# MM8I_Mk2.net
KiCad netlist of a schematic drawn in EAGLE
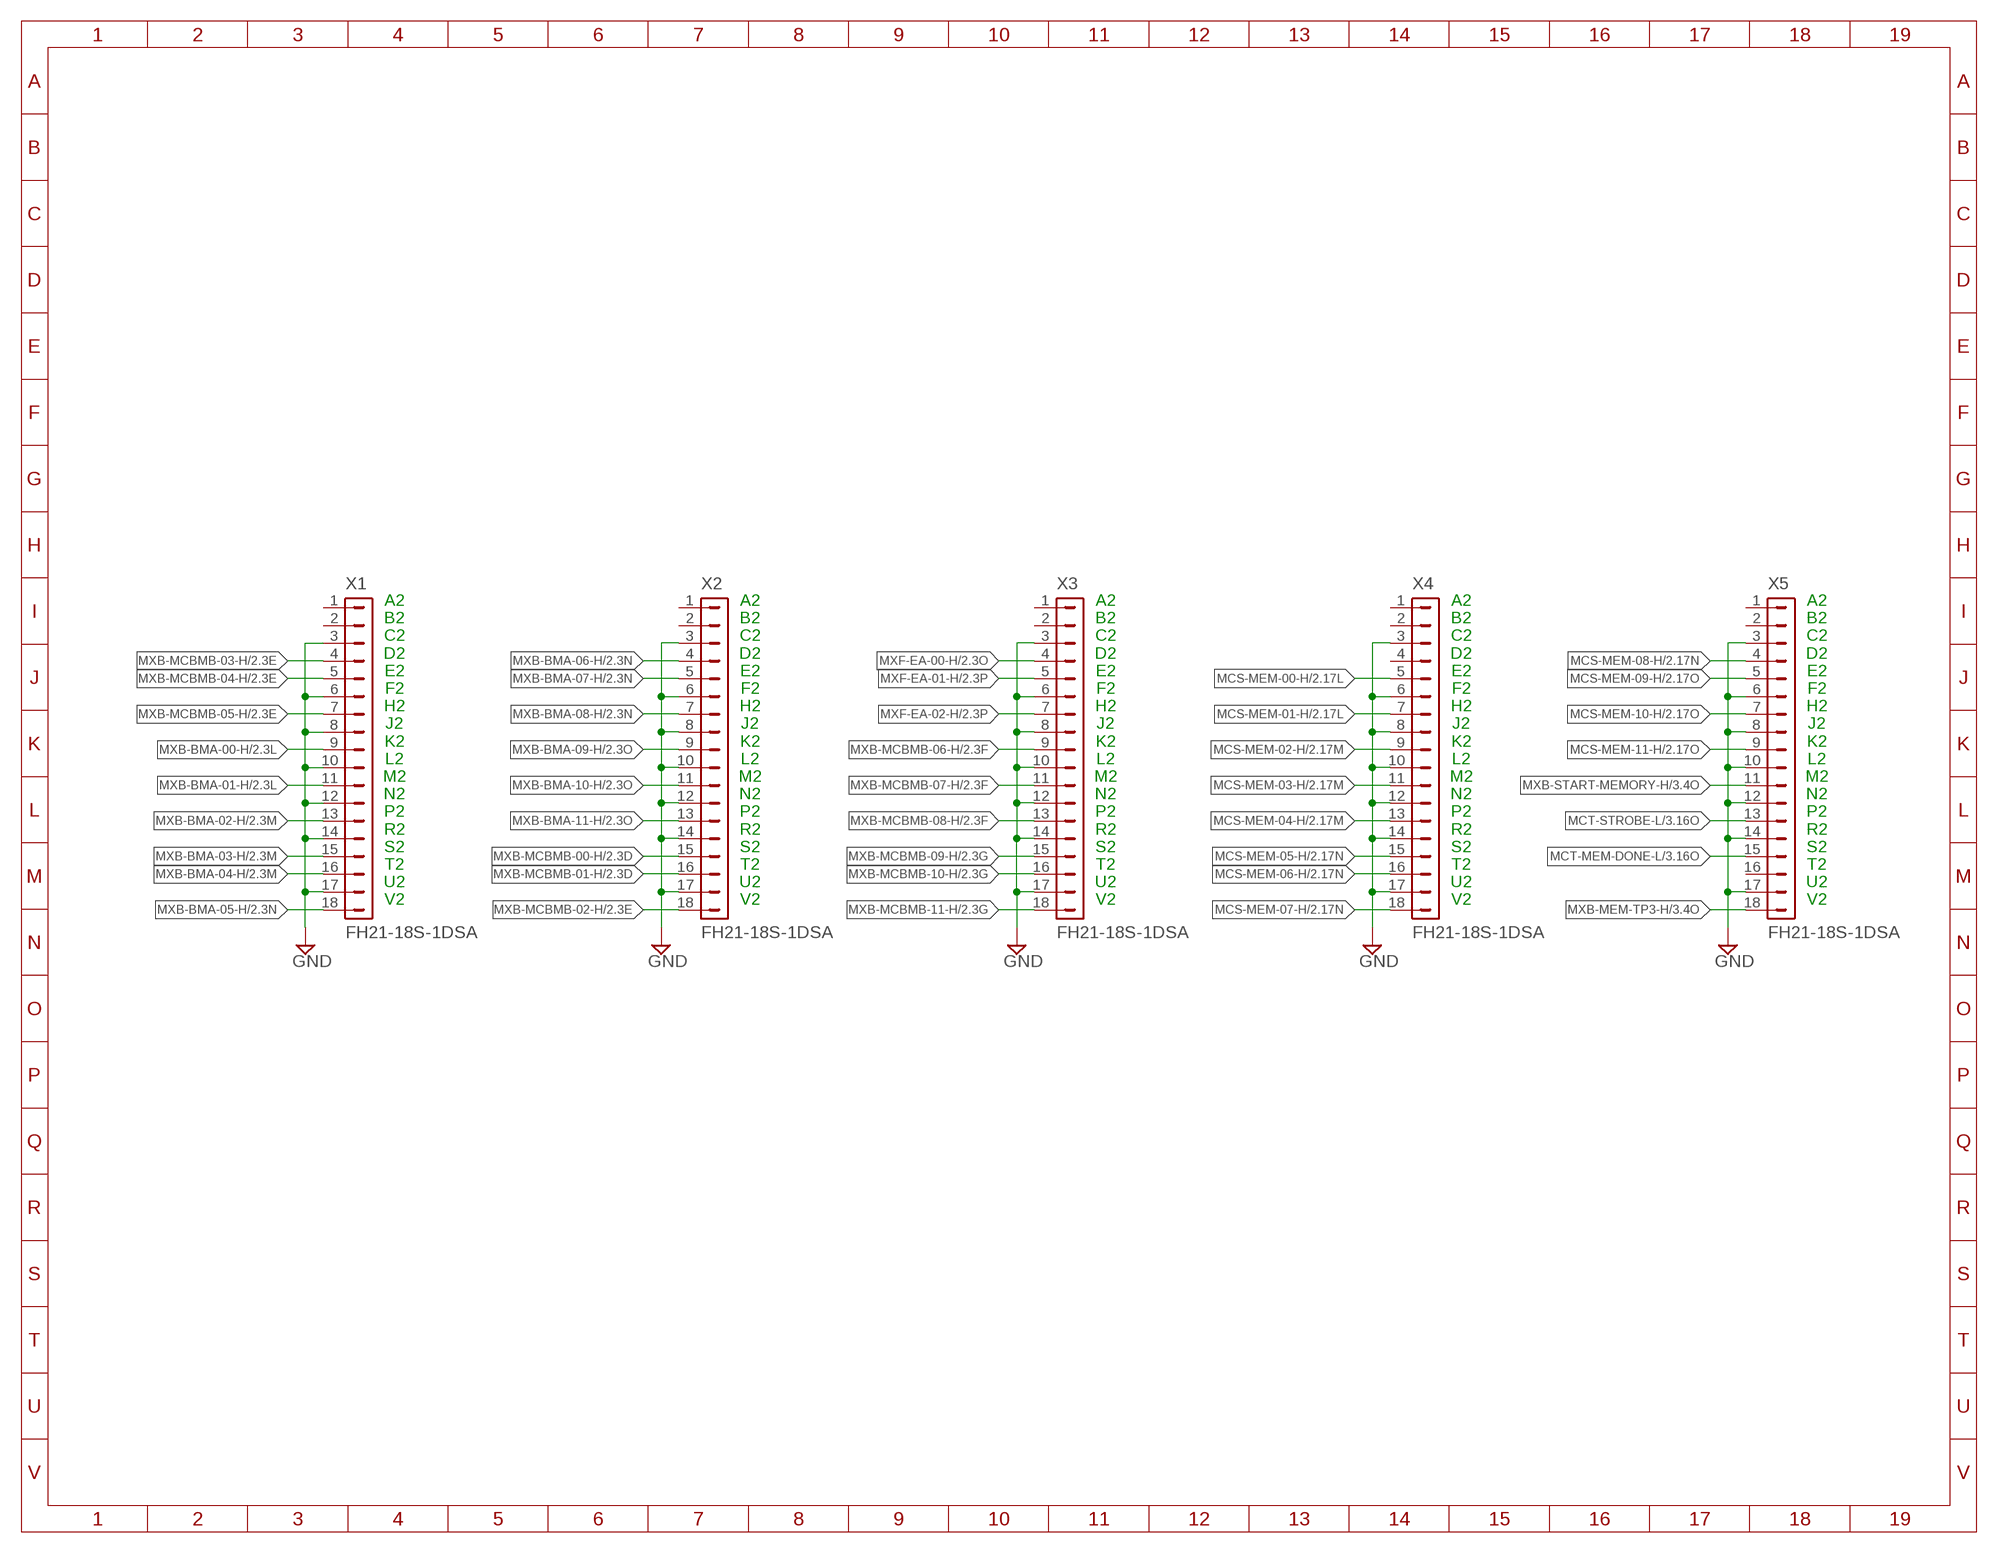
[diagram p0: schematic, sheet 1]
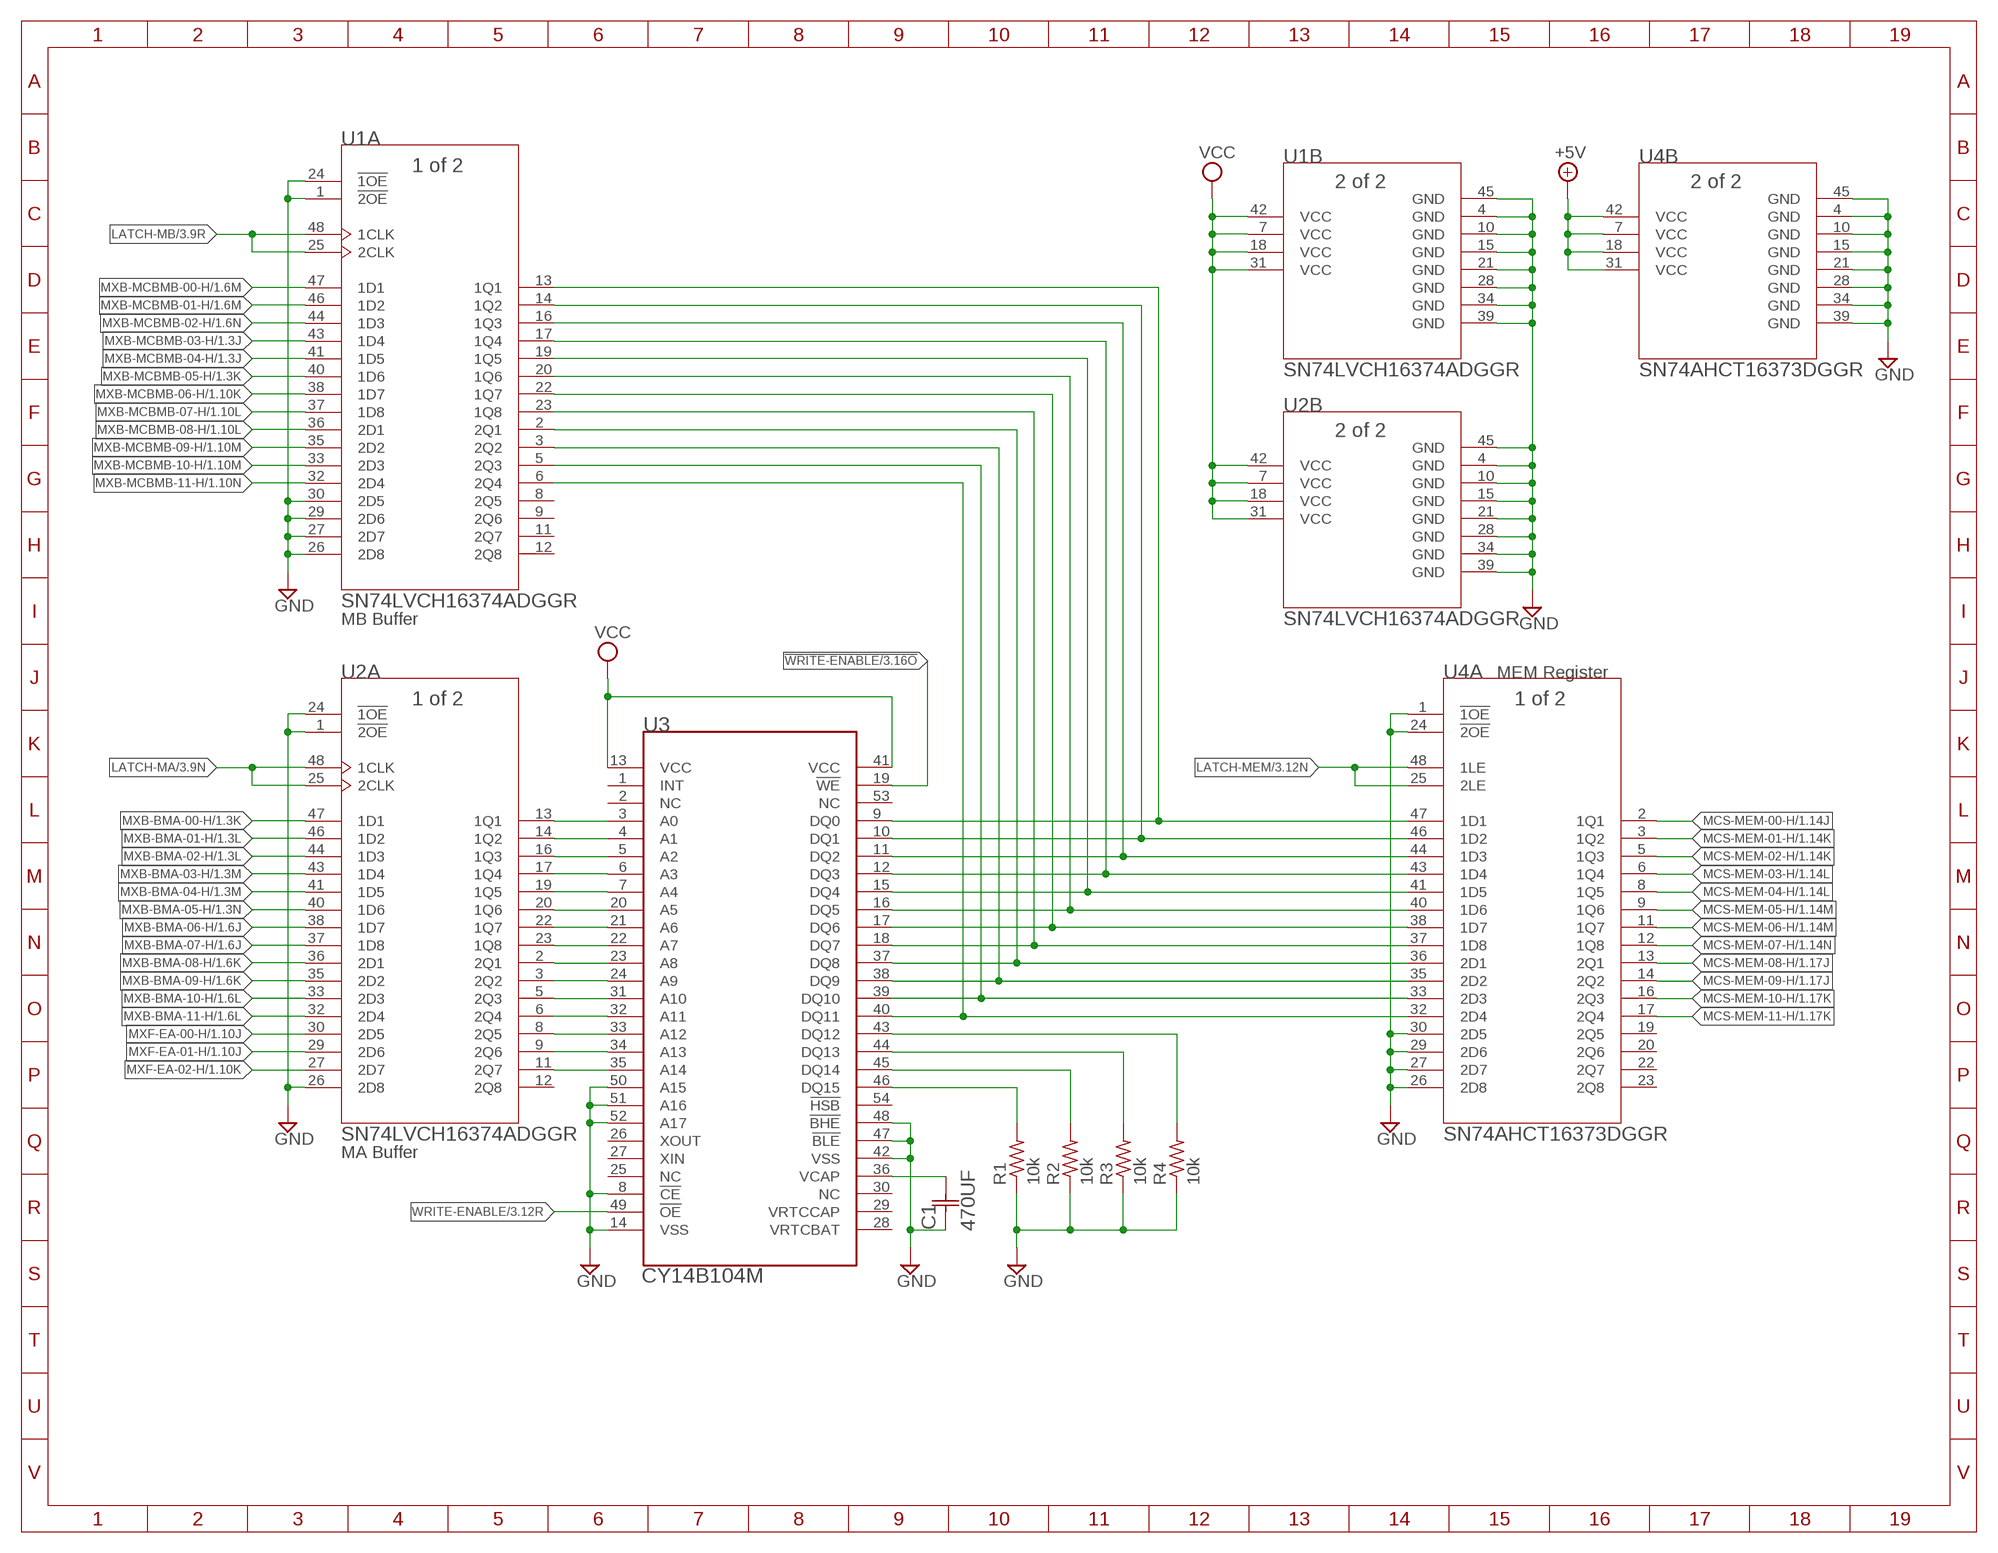
[diagram p1: schematic, sheet 2]
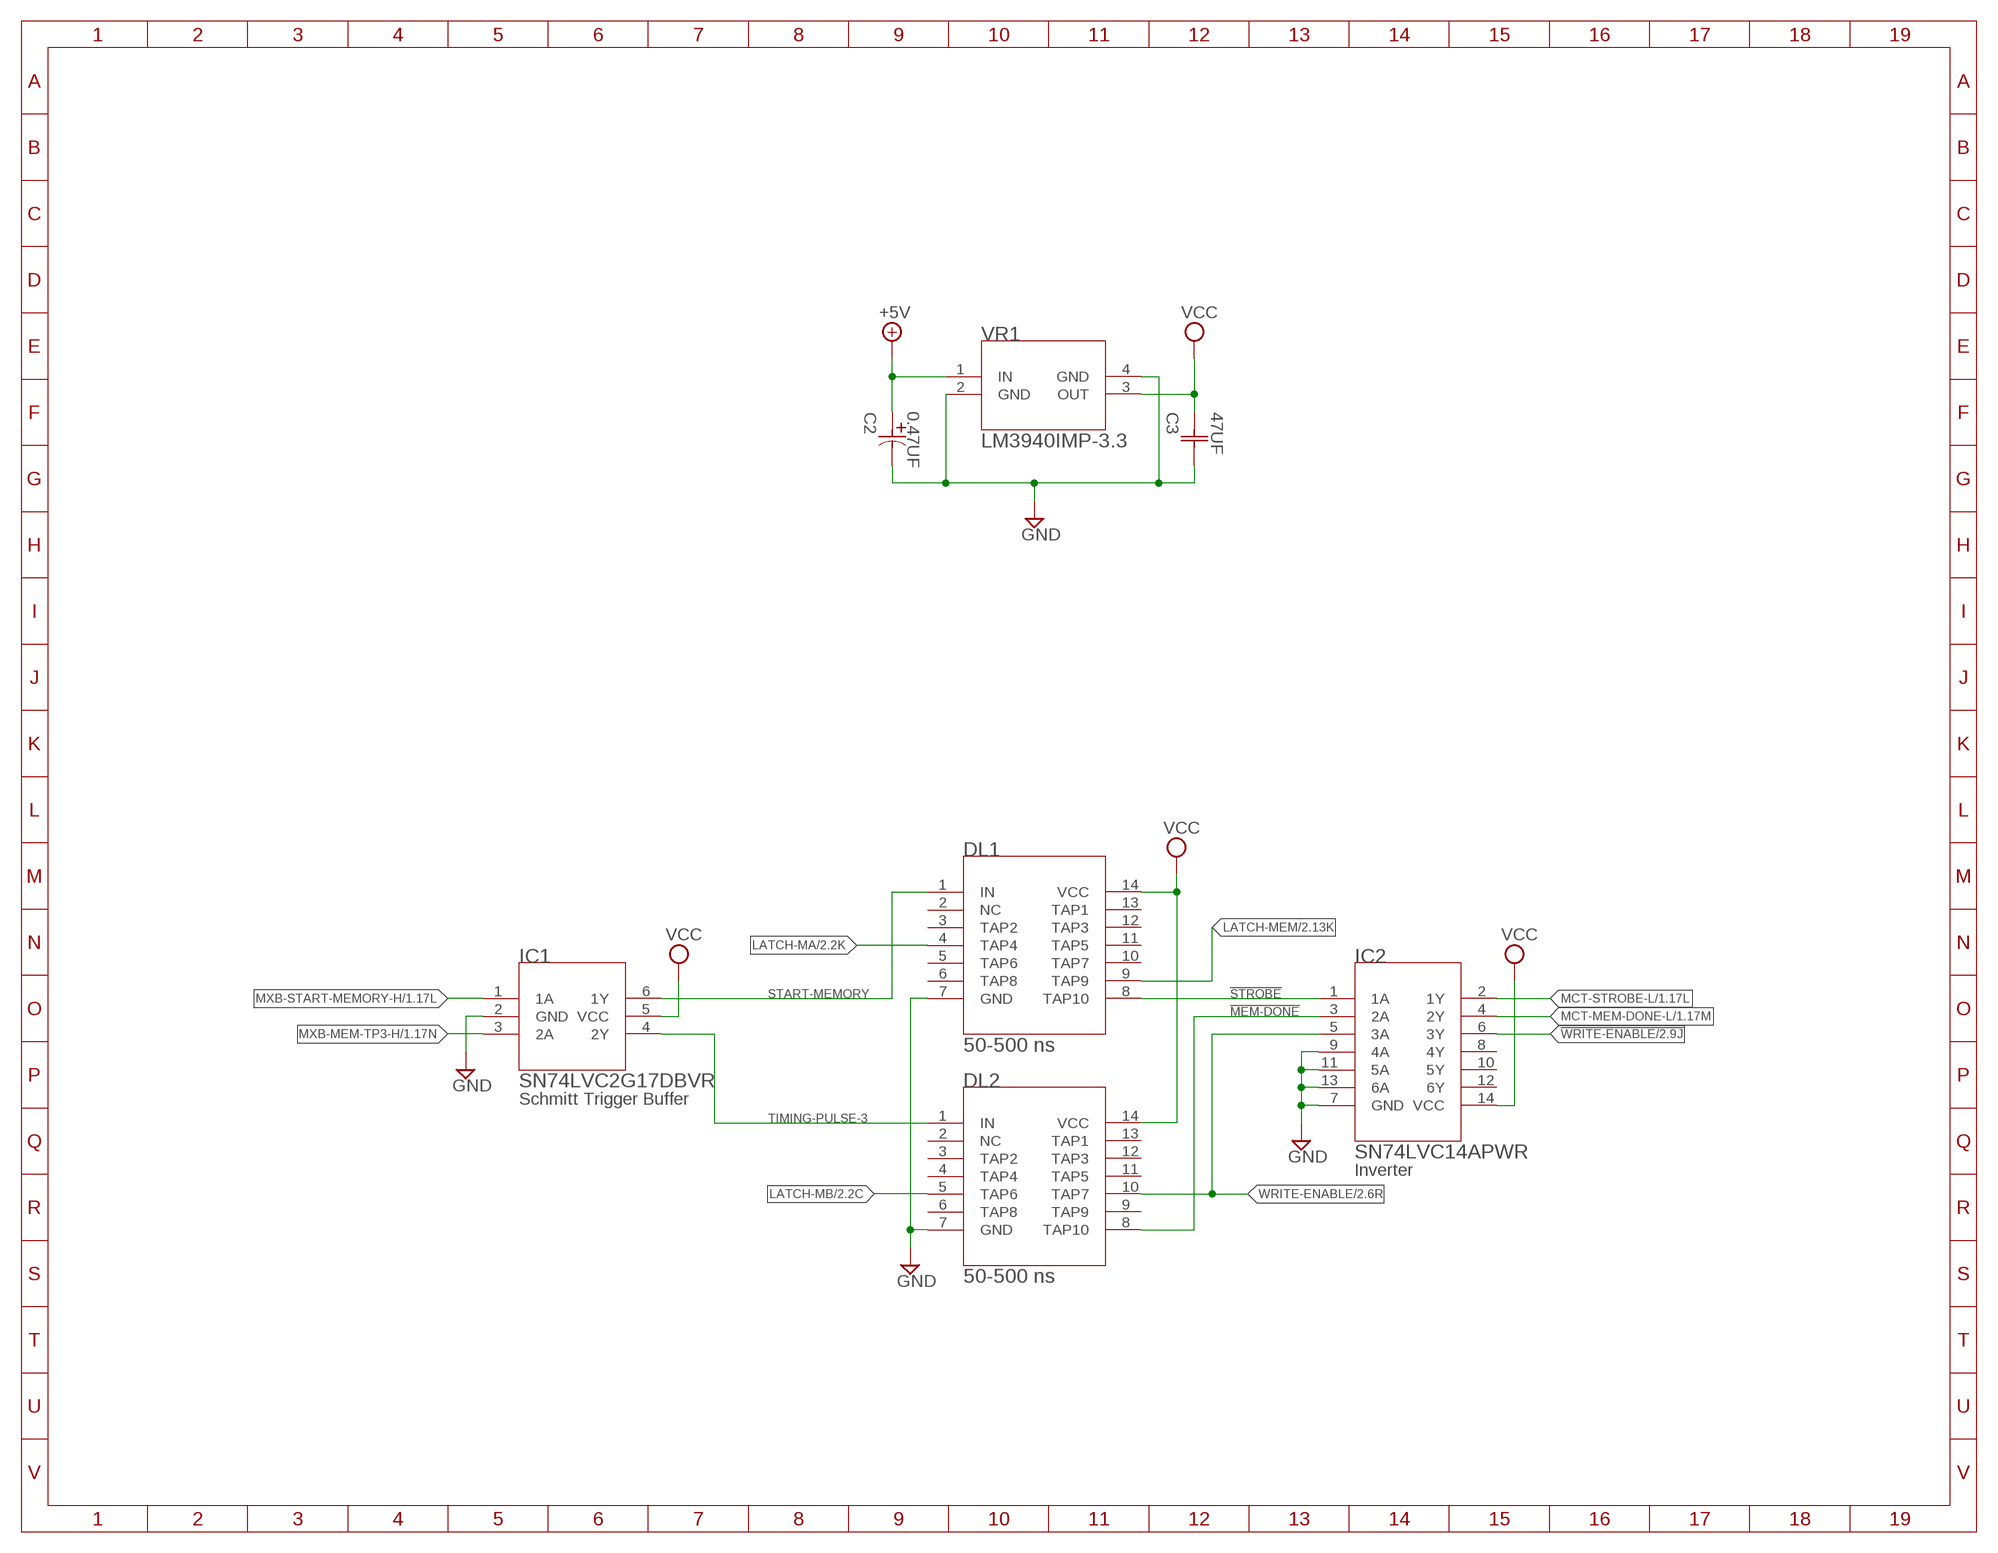
[diagram p2: schematic, sheet 3]

(export (version "E")
  (design (tool "Eeschema 10.0.6"))
  (components
    (comp (ref "X1")
      (value "FH21-18S-1DSA")
      (footprint "eagle-import:FH21-18S-1DSA")
      (libsource (lib "eagle-import") (part "FH21-18S-1DSA"))
    )
    (comp (ref "X2")
      (value "FH21-18S-1DSA")
      (footprint "eagle-import:FH21-18S-1DSA")
      (libsource (lib "eagle-import") (part "FH21-18S-1DSA"))
    )
    (comp (ref "X3")
      (value "FH21-18S-1DSA")
      (footprint "eagle-import:FH21-18S-1DSA")
      (libsource (lib "eagle-import") (part "FH21-18S-1DSA"))
    )
    (comp (ref "X4")
      (value "FH21-18S-1DSA")
      (footprint "eagle-import:FH21-18S-1DSA")
      (libsource (lib "eagle-import") (part "FH21-18S-1DSA"))
    )
    (comp (ref "X5")
      (value "FH21-18S-1DSA")
      (footprint "eagle-import:FH21-18S-1DSA")
      (libsource (lib "eagle-import") (part "FH21-18S-1DSA"))
    )
    (comp (ref "C1")
      (value "470UF")
      (footprint "eagle-import:CAPCP7343X430N")
      (fields (field (name "MPN") "NOSE477M004R0100"))
      (libsource (lib "eagle-import") (part "NOSE477M004R0100"))
    )
    (comp (ref "R1")
      (value "10k")
      (footprint "eagle-import:R1206")
      (libsource (lib "eagle-import") (part "R-US_R1206"))
    )
    (comp (ref "R2")
      (value "10k")
      (footprint "eagle-import:R1206")
      (libsource (lib "eagle-import") (part "R-US_R1206"))
    )
    (comp (ref "R3")
      (value "10k")
      (footprint "eagle-import:R1206")
      (libsource (lib "eagle-import") (part "R-US_R1206"))
    )
    (comp (ref "R4")
      (value "10k")
      (footprint "eagle-import:R1206")
      (libsource (lib "eagle-import") (part "R-US_R1206"))
    )
    (comp (ref "U1")
      (value "SN74LVCH16374ADGGR")
      (footprint "eagle-import:DGG48")
      (libsource (lib "eagle-import") (part "SN74LVCH16374ADGGR"))
    )
    (comp (ref "U2")
      (value "SN74LVCH16374ADGGR")
      (footprint "eagle-import:DGG48")
      (libsource (lib "eagle-import") (part "SN74LVCH16374ADGGR"))
    )
    (comp (ref "U3")
      (value "CY14B104M")
      (footprint "eagle-import:TSOPII-54")
      (libsource (lib "eagle-import") (part "CY14B104M"))
    )
    (comp (ref "U4")
      (value "SN74AHCT16373DGGR")
      (footprint "eagle-import:DGG48")
      (fields (field (name "MANUFACTURER") "Texas Instruments"))
      (libsource (lib "eagle-import") (part "SN74AHCT16373DGGR"))
    )
    (comp (ref "C2")
      (value "0.47UF")
      (footprint "eagle-import:CC0603N")
      (fields (field (name "MANUFACTURER_PART_NUMBER") "C0603C474K8PACTU"))
      (libsource (lib "eagle-import") (part "C0603C474K8PACTU"))
    )
    (comp (ref "C3")
      (value "47UF")
      (footprint "eagle-import:NOJC")
      (fields (field (name "MANUFACTURER_PART_NUMBER") "NOJC476M010RWJ"))
      (libsource (lib "eagle-import") (part "NOJC476M010RWJ"))
    )
    (comp (ref "DL1")
      (value "50-500 ns")
      (footprint "eagle-import:21-0066J_14")
      (fields (field (name "MANUFACTURER_PART_NUMBER") "DS1110LE-100+"))
      (libsource (lib "eagle-import") (part "DS1110LE-500+"))
    )
    (comp (ref "DL2")
      (value "50-500 ns")
      (footprint "eagle-import:21-0066J_14")
      (fields (field (name "MANUFACTURER_PART_NUMBER") "DS1110LE-100+"))
      (libsource (lib "eagle-import") (part "DS1110LE-500+"))
    )
    (comp (ref "IC1")
      (value "SN74LVC2G17DBVR")
      (footprint "eagle-import:DBV6")
      (fields (field (name "MANUFACTURER") "Texas Instruments"))
      (libsource (lib "eagle-import") (part "SN74LVC2G17DBVR"))
    )
    (comp (ref "IC2")
      (value "SN74LVC14APWR")
      (footprint "eagle-import:PW14")
      (fields (field (name "MANUFACTURER") "Texas Instruments"))
      (libsource (lib "eagle-import") (part "SN74LVC14APWR"))
    )
    (comp (ref "VR1")
      (value "LM3940IMP-3.3")
      (footprint "eagle-import:MP04A")
      (fields (field (name "MANUFACTURER_PART_NUMBER") "LM3940IMP-3.3/NOPB"))
      (libsource (lib "eagle-import") (part "LM3940IMP-3.3"))
    )
  )
  (nets
    (net (code "1") (name "+5V") (class "Default")
      (node (ref "C2") (pin "1") (pinfunction "1_1") (pintype "passive"))
      (node (ref "U4") (pin "18") (pinfunction "VCC_18") (pintype "power_in"))
      (node (ref "U4") (pin "31") (pinfunction "VCC_31") (pintype "power_in"))
      (node (ref "U4") (pin "42") (pinfunction "VCC_42") (pintype "power_in"))
      (node (ref "U4") (pin "7") (pinfunction "VCC_7") (pintype "power_in"))
      (node (ref "VR1") (pin "1") (pinfunction "IN_1") (pintype "input"))
    )
    (net (code "2") (name "GND") (class "Default")
      (node (ref "C1") (pin "2") (pinfunction "C2_2") (pintype "passive"))
      (node (ref "C2") (pin "2") (pinfunction "2_2") (pintype "passive"))
      (node (ref "C3") (pin "2") (pinfunction "C2_2") (pintype "passive"))
      (node (ref "DL1") (pin "7") (pinfunction "GND_7") (pintype "power_in"))
      (node (ref "DL2") (pin "7") (pinfunction "GND_7") (pintype "power_in"))
      (node (ref "IC1") (pin "2") (pinfunction "GND_2") (pintype "power_in"))
      (node (ref "IC2") (pin "11") (pinfunction "5A_11") (pintype "input"))
      (node (ref "IC2") (pin "13") (pinfunction "6A_13") (pintype "input"))
      (node (ref "IC2") (pin "7") (pinfunction "GND_7") (pintype "power_in"))
      (node (ref "IC2") (pin "9") (pinfunction "4A_9") (pintype "input"))
      (node (ref "R1") (pin "1") (pinfunction "1_1") (pintype "passive"))
      (node (ref "R2") (pin "1") (pinfunction "1_1") (pintype "passive"))
      (node (ref "R3") (pin "1") (pinfunction "1_1") (pintype "passive"))
      (node (ref "R4") (pin "1") (pinfunction "1_1") (pintype "passive"))
      (node (ref "U1") (pin "1") (pinfunction "~{2OE}_1") (pintype "input"))
      (node (ref "U1") (pin "10") (pinfunction "GND_10") (pintype "power_in"))
      (node (ref "U1") (pin "15") (pinfunction "GND_15") (pintype "power_in"))
      (node (ref "U1") (pin "21") (pinfunction "GND_21") (pintype "power_in"))
      (node (ref "U1") (pin "24") (pinfunction "~{1OE}_24") (pintype "input"))
      (node (ref "U1") (pin "26") (pinfunction "2D8_26") (pintype "input"))
      (node (ref "U1") (pin "27") (pinfunction "2D7_27") (pintype "input"))
      (node (ref "U1") (pin "28") (pinfunction "GND_28") (pintype "power_in"))
      (node (ref "U1") (pin "29") (pinfunction "2D6_29") (pintype "input"))
      (node (ref "U1") (pin "30") (pinfunction "2D5_30") (pintype "input"))
      (node (ref "U1") (pin "34") (pinfunction "GND_34") (pintype "power_in"))
      (node (ref "U1") (pin "39") (pinfunction "GND_39") (pintype "power_in"))
      (node (ref "U1") (pin "4") (pinfunction "GND_4") (pintype "power_in"))
      (node (ref "U1") (pin "45") (pinfunction "GND_45") (pintype "power_in"))
      (node (ref "U2") (pin "1") (pinfunction "~{2OE}_1") (pintype "input"))
      (node (ref "U2") (pin "10") (pinfunction "GND_10") (pintype "power_in"))
      (node (ref "U2") (pin "15") (pinfunction "GND_15") (pintype "power_in"))
      (node (ref "U2") (pin "21") (pinfunction "GND_21") (pintype "power_in"))
      (node (ref "U2") (pin "24") (pinfunction "~{1OE}_24") (pintype "input"))
      (node (ref "U2") (pin "26") (pinfunction "2D8_26") (pintype "input"))
      (node (ref "U2") (pin "28") (pinfunction "GND_28") (pintype "power_in"))
      (node (ref "U2") (pin "34") (pinfunction "GND_34") (pintype "power_in"))
      (node (ref "U2") (pin "39") (pinfunction "GND_39") (pintype "power_in"))
      (node (ref "U2") (pin "4") (pinfunction "GND_4") (pintype "power_in"))
      (node (ref "U2") (pin "45") (pinfunction "GND_45") (pintype "power_in"))
      (node (ref "U3") (pin "14") (pinfunction "VSS_14") (pintype "power_in"))
      (node (ref "U3") (pin "42") (pinfunction "VSS_42") (pintype "power_in"))
      (node (ref "U3") (pin "47") (pinfunction "~{BLE}_47") (pintype "input"))
      (node (ref "U3") (pin "48") (pinfunction "~{BHE}_48") (pintype "input"))
      (node (ref "U3") (pin "50") (pinfunction "A15_50") (pintype "input"))
      (node (ref "U3") (pin "51") (pinfunction "A16_51") (pintype "input"))
      (node (ref "U3") (pin "52") (pinfunction "A17_52") (pintype "input"))
      (node (ref "U3") (pin "8") (pinfunction "~{CE}_8") (pintype "bidirectional"))
      (node (ref "U4") (pin "1") (pinfunction "~{1OE}_1") (pintype "input"))
      (node (ref "U4") (pin "10") (pinfunction "GND_10") (pintype "power_in"))
      (node (ref "U4") (pin "15") (pinfunction "GND_15") (pintype "power_in"))
      (node (ref "U4") (pin "21") (pinfunction "GND_21") (pintype "power_in"))
      (node (ref "U4") (pin "24") (pinfunction "~{2OE}_24") (pintype "input"))
      (node (ref "U4") (pin "26") (pinfunction "2D8_26") (pintype "input"))
      (node (ref "U4") (pin "27") (pinfunction "2D7_27") (pintype "input"))
      (node (ref "U4") (pin "28") (pinfunction "GND_28") (pintype "power_in"))
      (node (ref "U4") (pin "29") (pinfunction "2D6_29") (pintype "input"))
      (node (ref "U4") (pin "30") (pinfunction "2D5_30") (pintype "input"))
      (node (ref "U4") (pin "34") (pinfunction "GND_34") (pintype "power_in"))
      (node (ref "U4") (pin "39") (pinfunction "GND_39") (pintype "power_in"))
      (node (ref "U4") (pin "4") (pinfunction "GND_4") (pintype "power_in"))
      (node (ref "U4") (pin "45") (pinfunction "GND_45") (pintype "power_in"))
      (node (ref "VR1") (pin "2") (pinfunction "GND_2") (pintype "passive"))
      (node (ref "VR1") (pin "4") (pinfunction "GND_4") (pintype "passive"))
      (node (ref "X1") (pin "10") (pinfunction "10_10") (pintype "passive"))
      (node (ref "X1") (pin "12") (pinfunction "12_12") (pintype "passive"))
      (node (ref "X1") (pin "14") (pinfunction "14_14") (pintype "passive"))
      (node (ref "X1") (pin "17") (pinfunction "17_17") (pintype "passive"))
      (node (ref "X1") (pin "3") (pinfunction "3_3") (pintype "passive"))
      (node (ref "X1") (pin "6") (pinfunction "6_6") (pintype "passive"))
      (node (ref "X1") (pin "8") (pinfunction "8_8") (pintype "passive"))
      (node (ref "X2") (pin "10") (pinfunction "10_10") (pintype "passive"))
      (node (ref "X2") (pin "12") (pinfunction "12_12") (pintype "passive"))
      (node (ref "X2") (pin "14") (pinfunction "14_14") (pintype "passive"))
      (node (ref "X2") (pin "17") (pinfunction "17_17") (pintype "passive"))
      (node (ref "X2") (pin "3") (pinfunction "3_3") (pintype "passive"))
      (node (ref "X2") (pin "6") (pinfunction "6_6") (pintype "passive"))
      (node (ref "X2") (pin "8") (pinfunction "8_8") (pintype "passive"))
      (node (ref "X3") (pin "10") (pinfunction "10_10") (pintype "passive"))
      (node (ref "X3") (pin "12") (pinfunction "12_12") (pintype "passive"))
      (node (ref "X3") (pin "14") (pinfunction "14_14") (pintype "passive"))
      (node (ref "X3") (pin "17") (pinfunction "17_17") (pintype "passive"))
      (node (ref "X3") (pin "3") (pinfunction "3_3") (pintype "passive"))
      (node (ref "X3") (pin "6") (pinfunction "6_6") (pintype "passive"))
      (node (ref "X3") (pin "8") (pinfunction "8_8") (pintype "passive"))
      (node (ref "X4") (pin "10") (pinfunction "10_10") (pintype "passive"))
      (node (ref "X4") (pin "12") (pinfunction "12_12") (pintype "passive"))
      (node (ref "X4") (pin "14") (pinfunction "14_14") (pintype "passive"))
      (node (ref "X4") (pin "17") (pinfunction "17_17") (pintype "passive"))
      (node (ref "X4") (pin "3") (pinfunction "3_3") (pintype "passive"))
      (node (ref "X4") (pin "6") (pinfunction "6_6") (pintype "passive"))
      (node (ref "X4") (pin "8") (pinfunction "8_8") (pintype "passive"))
      (node (ref "X5") (pin "10") (pinfunction "10_10") (pintype "passive"))
      (node (ref "X5") (pin "12") (pinfunction "12_12") (pintype "passive"))
      (node (ref "X5") (pin "14") (pinfunction "14_14") (pintype "passive"))
      (node (ref "X5") (pin "17") (pinfunction "17_17") (pintype "passive"))
      (node (ref "X5") (pin "3") (pinfunction "3_3") (pintype "passive"))
      (node (ref "X5") (pin "6") (pinfunction "6_6") (pintype "passive"))
      (node (ref "X5") (pin "8") (pinfunction "8_8") (pintype "passive"))
    )
    (net (code "3") (name "LATCH-MA") (class "Default")
      (node (ref "DL1") (pin "4") (pinfunction "TAP4_4") (pintype "output"))
      (node (ref "U2") (pin "25") (pinfunction "2CLK_25") (pintype "input"))
      (node (ref "U2") (pin "48") (pinfunction "1CLK_48") (pintype "input"))
    )
    (net (code "4") (name "LATCH-MB") (class "Default")
      (node (ref "DL2") (pin "5") (pinfunction "TAP6_5") (pintype "output"))
      (node (ref "U1") (pin "25") (pinfunction "2CLK_25") (pintype "input"))
      (node (ref "U1") (pin "48") (pinfunction "1CLK_48") (pintype "input"))
    )
    (net (code "5") (name "LATCH-MEM") (class "Default")
      (node (ref "DL1") (pin "9") (pinfunction "TAP9_9") (pintype "output"))
      (node (ref "U4") (pin "25") (pinfunction "2LE_25") (pintype "input"))
      (node (ref "U4") (pin "48") (pinfunction "1LE_48") (pintype "input"))
    )
    (net (code "6") (name "MCS-MEM-00-H") (class "Default")
      (node (ref "U4") (pin "2") (pinfunction "1Q1_2") (pintype "output"))
      (node (ref "X4") (pin "5") (pinfunction "5_5") (pintype "passive"))
    )
    (net (code "7") (name "MCS-MEM-01-H") (class "Default")
      (node (ref "U4") (pin "3") (pinfunction "1Q2_3") (pintype "output"))
      (node (ref "X4") (pin "7") (pinfunction "7_7") (pintype "passive"))
    )
    (net (code "8") (name "MCS-MEM-02-H") (class "Default")
      (node (ref "U4") (pin "5") (pinfunction "1Q3_5") (pintype "output"))
      (node (ref "X4") (pin "9") (pinfunction "9_9") (pintype "passive"))
    )
    (net (code "9") (name "MCS-MEM-03-H") (class "Default")
      (node (ref "U4") (pin "6") (pinfunction "1Q4_6") (pintype "output"))
      (node (ref "X4") (pin "11") (pinfunction "11_11") (pintype "passive"))
    )
    (net (code "10") (name "MCS-MEM-04-H") (class "Default")
      (node (ref "U4") (pin "8") (pinfunction "1Q5_8") (pintype "output"))
      (node (ref "X4") (pin "13") (pinfunction "13_13") (pintype "passive"))
    )
    (net (code "11") (name "MCS-MEM-05-H") (class "Default")
      (node (ref "U4") (pin "9") (pinfunction "1Q6_9") (pintype "output"))
      (node (ref "X4") (pin "15") (pinfunction "15_15") (pintype "passive"))
    )
    (net (code "12") (name "MCS-MEM-06-H") (class "Default")
      (node (ref "U4") (pin "11") (pinfunction "1Q7_11") (pintype "output"))
      (node (ref "X4") (pin "16") (pinfunction "16_16") (pintype "passive"))
    )
    (net (code "13") (name "MCS-MEM-07-H") (class "Default")
      (node (ref "U4") (pin "12") (pinfunction "1Q8_12") (pintype "output"))
      (node (ref "X4") (pin "18") (pinfunction "18_18") (pintype "passive"))
    )
    (net (code "14") (name "MCS-MEM-08-H") (class "Default")
      (node (ref "U4") (pin "13") (pinfunction "2Q1_13") (pintype "output"))
      (node (ref "X5") (pin "4") (pinfunction "4_4") (pintype "passive"))
    )
    (net (code "15") (name "MCS-MEM-09-H") (class "Default")
      (node (ref "U4") (pin "14") (pinfunction "2Q2_14") (pintype "output"))
      (node (ref "X5") (pin "5") (pinfunction "5_5") (pintype "passive"))
    )
    (net (code "16") (name "MCS-MEM-10-H") (class "Default")
      (node (ref "U4") (pin "16") (pinfunction "2Q3_16") (pintype "output"))
      (node (ref "X5") (pin "7") (pinfunction "7_7") (pintype "passive"))
    )
    (net (code "17") (name "MCS-MEM-11-H") (class "Default")
      (node (ref "U4") (pin "17") (pinfunction "2Q4_17") (pintype "output"))
      (node (ref "X5") (pin "9") (pinfunction "9_9") (pintype "passive"))
    )
    (net (code "18") (name "MCT-MEM-DONE-L") (class "Default")
      (node (ref "IC2") (pin "4") (pinfunction "2Y_4") (pintype "output"))
      (node (ref "X5") (pin "15") (pinfunction "15_15") (pintype "passive"))
    )
    (net (code "19") (name "MCT-STROBE-L") (class "Default")
      (node (ref "IC2") (pin "2") (pinfunction "1Y_2") (pintype "output"))
      (node (ref "X5") (pin "13") (pinfunction "13_13") (pintype "passive"))
    )
    (net (code "20") (name "MXB-BMA-00-H") (class "Default")
      (node (ref "U2") (pin "47") (pinfunction "1D1_47") (pintype "input"))
      (node (ref "X1") (pin "9") (pinfunction "9_9") (pintype "passive"))
    )
    (net (code "21") (name "MXB-BMA-01-H") (class "Default")
      (node (ref "U2") (pin "46") (pinfunction "1D2_46") (pintype "input"))
      (node (ref "X1") (pin "11") (pinfunction "11_11") (pintype "passive"))
    )
    (net (code "22") (name "MXB-BMA-02-H") (class "Default")
      (node (ref "U2") (pin "44") (pinfunction "1D3_44") (pintype "input"))
      (node (ref "X1") (pin "13") (pinfunction "13_13") (pintype "passive"))
    )
    (net (code "23") (name "MXB-BMA-03-H") (class "Default")
      (node (ref "U2") (pin "43") (pinfunction "1D4_43") (pintype "input"))
      (node (ref "X1") (pin "15") (pinfunction "15_15") (pintype "passive"))
    )
    (net (code "24") (name "MXB-BMA-04-H") (class "Default")
      (node (ref "U2") (pin "41") (pinfunction "1D5_41") (pintype "input"))
      (node (ref "X1") (pin "16") (pinfunction "16_16") (pintype "passive"))
    )
    (net (code "25") (name "MXB-BMA-05-H") (class "Default")
      (node (ref "U2") (pin "40") (pinfunction "1D6_40") (pintype "input"))
      (node (ref "X1") (pin "18") (pinfunction "18_18") (pintype "passive"))
    )
    (net (code "26") (name "MXB-BMA-06-H") (class "Default")
      (node (ref "U2") (pin "38") (pinfunction "1D7_38") (pintype "input"))
      (node (ref "X2") (pin "4") (pinfunction "4_4") (pintype "passive"))
    )
    (net (code "27") (name "MXB-BMA-07-H") (class "Default")
      (node (ref "U2") (pin "37") (pinfunction "1D8_37") (pintype "input"))
      (node (ref "X2") (pin "5") (pinfunction "5_5") (pintype "passive"))
    )
    (net (code "28") (name "MXB-BMA-08-H") (class "Default")
      (node (ref "U2") (pin "36") (pinfunction "2D1_36") (pintype "input"))
      (node (ref "X2") (pin "7") (pinfunction "7_7") (pintype "passive"))
    )
    (net (code "29") (name "MXB-BMA-09-H") (class "Default")
      (node (ref "U2") (pin "35") (pinfunction "2D2_35") (pintype "input"))
      (node (ref "X2") (pin "9") (pinfunction "9_9") (pintype "passive"))
    )
    (net (code "30") (name "MXB-BMA-10-H") (class "Default")
      (node (ref "U2") (pin "33") (pinfunction "2D3_33") (pintype "input"))
      (node (ref "X2") (pin "11") (pinfunction "11_11") (pintype "passive"))
    )
    (net (code "31") (name "MXB-BMA-11-H") (class "Default")
      (node (ref "U2") (pin "32") (pinfunction "2D4_32") (pintype "input"))
      (node (ref "X2") (pin "13") (pinfunction "13_13") (pintype "passive"))
    )
    (net (code "32") (name "MXB-MCBMB-00-H") (class "Default")
      (node (ref "U1") (pin "47") (pinfunction "1D1_47") (pintype "input"))
      (node (ref "X2") (pin "15") (pinfunction "15_15") (pintype "passive"))
    )
    (net (code "33") (name "MXB-MCBMB-01-H") (class "Default")
      (node (ref "U1") (pin "46") (pinfunction "1D2_46") (pintype "input"))
      (node (ref "X2") (pin "16") (pinfunction "16_16") (pintype "passive"))
    )
    (net (code "34") (name "MXB-MCBMB-02-H") (class "Default")
      (node (ref "U1") (pin "44") (pinfunction "1D3_44") (pintype "input"))
      (node (ref "X2") (pin "18") (pinfunction "18_18") (pintype "passive"))
    )
    (net (code "35") (name "MXB-MCBMB-03-H") (class "Default")
      (node (ref "U1") (pin "43") (pinfunction "1D4_43") (pintype "input"))
      (node (ref "X1") (pin "4") (pinfunction "4_4") (pintype "passive"))
    )
    (net (code "36") (name "MXB-MCBMB-04-H") (class "Default")
      (node (ref "U1") (pin "41") (pinfunction "1D5_41") (pintype "input"))
      (node (ref "X1") (pin "5") (pinfunction "5_5") (pintype "passive"))
    )
    (net (code "37") (name "MXB-MCBMB-05-H") (class "Default")
      (node (ref "U1") (pin "40") (pinfunction "1D6_40") (pintype "input"))
      (node (ref "X1") (pin "7") (pinfunction "7_7") (pintype "passive"))
    )
    (net (code "38") (name "MXB-MCBMB-06-H") (class "Default")
      (node (ref "U1") (pin "38") (pinfunction "1D7_38") (pintype "input"))
      (node (ref "X3") (pin "9") (pinfunction "9_9") (pintype "passive"))
    )
    (net (code "39") (name "MXB-MCBMB-07-H") (class "Default")
      (node (ref "U1") (pin "37") (pinfunction "1D8_37") (pintype "input"))
      (node (ref "X3") (pin "11") (pinfunction "11_11") (pintype "passive"))
    )
    (net (code "40") (name "MXB-MCBMB-08-H") (class "Default")
      (node (ref "U1") (pin "36") (pinfunction "2D1_36") (pintype "input"))
      (node (ref "X3") (pin "13") (pinfunction "13_13") (pintype "passive"))
    )
    (net (code "41") (name "MXB-MCBMB-09-H") (class "Default")
      (node (ref "U1") (pin "35") (pinfunction "2D2_35") (pintype "input"))
      (node (ref "X3") (pin "15") (pinfunction "15_15") (pintype "passive"))
    )
    (net (code "42") (name "MXB-MCBMB-10-H") (class "Default")
      (node (ref "U1") (pin "33") (pinfunction "2D3_33") (pintype "input"))
      (node (ref "X3") (pin "16") (pinfunction "16_16") (pintype "passive"))
    )
    (net (code "43") (name "MXB-MCBMB-11-H") (class "Default")
      (node (ref "U1") (pin "32") (pinfunction "2D4_32") (pintype "input"))
      (node (ref "X3") (pin "18") (pinfunction "18_18") (pintype "passive"))
    )
    (net (code "44") (name "MXB-MEM-TP3-H") (class "Default")
      (node (ref "IC1") (pin "3") (pinfunction "2A_3") (pintype "input"))
      (node (ref "X5") (pin "18") (pinfunction "18_18") (pintype "passive"))
    )
    (net (code "45") (name "MXB-START-MEMORY-H") (class "Default")
      (node (ref "IC1") (pin "1") (pinfunction "1A_1") (pintype "input"))
      (node (ref "X5") (pin "11") (pinfunction "11_11") (pintype "passive"))
    )
    (net (code "46") (name "MXF-EA-00-H") (class "Default")
      (node (ref "U2") (pin "30") (pinfunction "2D5_30") (pintype "input"))
      (node (ref "X3") (pin "4") (pinfunction "4_4") (pintype "passive"))
    )
    (net (code "47") (name "MXF-EA-01-H") (class "Default")
      (node (ref "U2") (pin "29") (pinfunction "2D6_29") (pintype "input"))
      (node (ref "X3") (pin "5") (pinfunction "5_5") (pintype "passive"))
    )
    (net (code "48") (name "MXF-EA-02-H") (class "Default")
      (node (ref "U2") (pin "27") (pinfunction "2D7_27") (pintype "input"))
      (node (ref "X3") (pin "7") (pinfunction "7_7") (pintype "passive"))
    )
    (net (code "49") (name "Net-(C1-C1)") (class "Default")
      (node (ref "C1") (pin "1") (pinfunction "C1_1") (pintype "passive"))
      (node (ref "U3") (pin "36") (pinfunction "VCAP_36") (pintype "output"))
    )
    (net (code "50") (name "Net-(U1A-1Q1)") (class "Default")
      (node (ref "U1") (pin "13") (pinfunction "1Q1_13") (pintype "output"))
      (node (ref "U3") (pin "9") (pinfunction "DQ0_9") (pintype "bidirectional"))
      (node (ref "U4") (pin "47") (pinfunction "1D1_47") (pintype "input"))
    )
    (net (code "51") (name "Net-(U1A-1Q2)") (class "Default")
      (node (ref "U1") (pin "14") (pinfunction "1Q2_14") (pintype "output"))
      (node (ref "U3") (pin "10") (pinfunction "DQ1_10") (pintype "bidirectional"))
      (node (ref "U4") (pin "46") (pinfunction "1D2_46") (pintype "input"))
    )
    (net (code "52") (name "Net-(U1A-1Q3)") (class "Default")
      (node (ref "U1") (pin "16") (pinfunction "1Q3_16") (pintype "output"))
      (node (ref "U3") (pin "11") (pinfunction "DQ2_11") (pintype "bidirectional"))
      (node (ref "U4") (pin "44") (pinfunction "1D3_44") (pintype "input"))
    )
    (net (code "53") (name "Net-(U1A-1Q4)") (class "Default")
      (node (ref "U1") (pin "17") (pinfunction "1Q4_17") (pintype "output"))
      (node (ref "U3") (pin "12") (pinfunction "DQ3_12") (pintype "bidirectional"))
      (node (ref "U4") (pin "43") (pinfunction "1D4_43") (pintype "input"))
    )
    (net (code "54") (name "Net-(U1A-1Q5)") (class "Default")
      (node (ref "U1") (pin "19") (pinfunction "1Q5_19") (pintype "output"))
      (node (ref "U3") (pin "15") (pinfunction "DQ4_15") (pintype "bidirectional"))
      (node (ref "U4") (pin "41") (pinfunction "1D5_41") (pintype "input"))
    )
    (net (code "55") (name "Net-(U1A-1Q6)") (class "Default")
      (node (ref "U1") (pin "20") (pinfunction "1Q6_20") (pintype "output"))
      (node (ref "U3") (pin "16") (pinfunction "DQ5_16") (pintype "bidirectional"))
      (node (ref "U4") (pin "40") (pinfunction "1D6_40") (pintype "input"))
    )
    (net (code "56") (name "Net-(U1A-1Q7)") (class "Default")
      (node (ref "U1") (pin "22") (pinfunction "1Q7_22") (pintype "output"))
      (node (ref "U3") (pin "17") (pinfunction "DQ6_17") (pintype "bidirectional"))
      (node (ref "U4") (pin "38") (pinfunction "1D7_38") (pintype "input"))
    )
    (net (code "57") (name "Net-(U1A-1Q8)") (class "Default")
      (node (ref "U1") (pin "23") (pinfunction "1Q8_23") (pintype "output"))
      (node (ref "U3") (pin "18") (pinfunction "DQ7_18") (pintype "bidirectional"))
      (node (ref "U4") (pin "37") (pinfunction "1D8_37") (pintype "input"))
    )
    (net (code "58") (name "Net-(U1A-2Q1)") (class "Default")
      (node (ref "U1") (pin "2") (pinfunction "2Q1_2") (pintype "output"))
      (node (ref "U3") (pin "37") (pinfunction "DQ8_37") (pintype "bidirectional"))
      (node (ref "U4") (pin "36") (pinfunction "2D1_36") (pintype "input"))
    )
    (net (code "59") (name "Net-(U1A-2Q2)") (class "Default")
      (node (ref "U1") (pin "3") (pinfunction "2Q2_3") (pintype "output"))
      (node (ref "U3") (pin "38") (pinfunction "DQ9_38") (pintype "bidirectional"))
      (node (ref "U4") (pin "35") (pinfunction "2D2_35") (pintype "input"))
    )
    (net (code "60") (name "Net-(U1A-2Q3)") (class "Default")
      (node (ref "U1") (pin "5") (pinfunction "2Q3_5") (pintype "output"))
      (node (ref "U3") (pin "39") (pinfunction "DQ10_39") (pintype "bidirectional"))
      (node (ref "U4") (pin "33") (pinfunction "2D3_33") (pintype "input"))
    )
    (net (code "61") (name "Net-(U1A-2Q4)") (class "Default")
      (node (ref "U1") (pin "6") (pinfunction "2Q4_6") (pintype "output"))
      (node (ref "U3") (pin "40") (pinfunction "DQ11_40") (pintype "bidirectional"))
      (node (ref "U4") (pin "32") (pinfunction "2D4_32") (pintype "input"))
    )
    (net (code "62") (name "Net-(U2A-1Q1)") (class "Default")
      (node (ref "U2") (pin "13") (pinfunction "1Q1_13") (pintype "output"))
      (node (ref "U3") (pin "3") (pinfunction "A0_3") (pintype "input"))
    )
    (net (code "63") (name "Net-(U2A-1Q2)") (class "Default")
      (node (ref "U2") (pin "14") (pinfunction "1Q2_14") (pintype "output"))
      (node (ref "U3") (pin "4") (pinfunction "A1_4") (pintype "input"))
    )
    (net (code "64") (name "Net-(U2A-1Q3)") (class "Default")
      (node (ref "U2") (pin "16") (pinfunction "1Q3_16") (pintype "output"))
      (node (ref "U3") (pin "5") (pinfunction "A2_5") (pintype "input"))
    )
    (net (code "65") (name "Net-(U2A-1Q4)") (class "Default")
      (node (ref "U2") (pin "17") (pinfunction "1Q4_17") (pintype "output"))
      (node (ref "U3") (pin "6") (pinfunction "A3_6") (pintype "input"))
    )
    (net (code "66") (name "Net-(U2A-1Q5)") (class "Default")
      (node (ref "U2") (pin "19") (pinfunction "1Q5_19") (pintype "output"))
      (node (ref "U3") (pin "7") (pinfunction "A4_7") (pintype "input"))
    )
    (net (code "67") (name "Net-(U2A-1Q6)") (class "Default")
      (node (ref "U2") (pin "20") (pinfunction "1Q6_20") (pintype "output"))
      (node (ref "U3") (pin "20") (pinfunction "A5_20") (pintype "input"))
    )
    (net (code "68") (name "Net-(U2A-1Q7)") (class "Default")
      (node (ref "U2") (pin "22") (pinfunction "1Q7_22") (pintype "output"))
      (node (ref "U3") (pin "21") (pinfunction "A6_21") (pintype "input"))
    )
    (net (code "69") (name "Net-(U2A-1Q8)") (class "Default")
      (node (ref "U2") (pin "23") (pinfunction "1Q8_23") (pintype "output"))
      (node (ref "U3") (pin "22") (pinfunction "A7_22") (pintype "input"))
    )
    (net (code "70") (name "Net-(U2A-2Q1)") (class "Default")
      (node (ref "U2") (pin "2") (pinfunction "2Q1_2") (pintype "output"))
      (node (ref "U3") (pin "23") (pinfunction "A8_23") (pintype "input"))
    )
    (net (code "71") (name "Net-(U2A-2Q2)") (class "Default")
      (node (ref "U2") (pin "3") (pinfunction "2Q2_3") (pintype "output"))
      (node (ref "U3") (pin "24") (pinfunction "A9_24") (pintype "input"))
    )
    (net (code "72") (name "Net-(U2A-2Q3)") (class "Default")
      (node (ref "U2") (pin "5") (pinfunction "2Q3_5") (pintype "output"))
      (node (ref "U3") (pin "31") (pinfunction "A10_31") (pintype "input"))
    )
    (net (code "73") (name "Net-(U2A-2Q4)") (class "Default")
      (node (ref "U2") (pin "6") (pinfunction "2Q4_6") (pintype "output"))
      (node (ref "U3") (pin "32") (pinfunction "A11_32") (pintype "input"))
    )
    (net (code "74") (name "Net-(U2A-2Q5)") (class "Default")
      (node (ref "U2") (pin "8") (pinfunction "2Q5_8") (pintype "output"))
      (node (ref "U3") (pin "33") (pinfunction "A12_33") (pintype "input"))
    )
    (net (code "75") (name "Net-(U2A-2Q6)") (class "Default")
      (node (ref "U2") (pin "9") (pinfunction "2Q6_9") (pintype "output"))
      (node (ref "U3") (pin "34") (pinfunction "A13_34") (pintype "input"))
    )
    (net (code "76") (name "Net-(U2A-2Q7)") (class "Default")
      (node (ref "U2") (pin "11") (pinfunction "2Q7_11") (pintype "output"))
      (node (ref "U3") (pin "35") (pinfunction "A14_35") (pintype "input"))
    )
    (net (code "77") (name "Net-(U3-DQ12)") (class "Default")
      (node (ref "R4") (pin "2") (pinfunction "2_2") (pintype "passive"))
      (node (ref "U3") (pin "43") (pinfunction "DQ12_43") (pintype "bidirectional"))
    )
    (net (code "78") (name "Net-(U3-DQ13)") (class "Default")
      (node (ref "R3") (pin "2") (pinfunction "2_2") (pintype "passive"))
      (node (ref "U3") (pin "44") (pinfunction "DQ13_44") (pintype "bidirectional"))
    )
    (net (code "79") (name "Net-(U3-DQ14)") (class "Default")
      (node (ref "R2") (pin "2") (pinfunction "2_2") (pintype "passive"))
      (node (ref "U3") (pin "45") (pinfunction "DQ14_45") (pintype "bidirectional"))
    )
    (net (code "80") (name "Net-(U3-DQ15)") (class "Default")
      (node (ref "R1") (pin "2") (pinfunction "2_2") (pintype "passive"))
      (node (ref "U3") (pin "46") (pinfunction "DQ15_46") (pintype "bidirectional"))
    )
    (net (code "81") (name "START-MEMORY") (class "Default")
      (node (ref "DL1") (pin "1") (pinfunction "IN_1") (pintype "input"))
      (node (ref "IC1") (pin "6") (pinfunction "1Y_6") (pintype "output"))
    )
    (net (code "82") (name "TIMING-PULSE-3") (class "Default")
      (node (ref "DL2") (pin "1") (pinfunction "IN_1") (pintype "input"))
      (node (ref "IC1") (pin "4") (pinfunction "2Y_4") (pintype "output"))
    )
    (net (code "83") (name "VCC") (class "Default")
      (node (ref "C3") (pin "1") (pinfunction "C1_1") (pintype "passive"))
      (node (ref "DL1") (pin "14") (pinfunction "VCC_14") (pintype "power_in"))
      (node (ref "DL2") (pin "14") (pinfunction "VCC_14") (pintype "power_in"))
      (node (ref "IC1") (pin "5") (pinfunction "VCC_5") (pintype "power_in"))
      (node (ref "IC2") (pin "14") (pinfunction "VCC_14") (pintype "power_in"))
      (node (ref "U1") (pin "18") (pinfunction "VCC_18") (pintype "power_in"))
      (node (ref "U1") (pin "31") (pinfunction "VCC_31") (pintype "power_in"))
      (node (ref "U1") (pin "42") (pinfunction "VCC_42") (pintype "power_in"))
      (node (ref "U1") (pin "7") (pinfunction "VCC_7") (pintype "power_in"))
      (node (ref "U2") (pin "18") (pinfunction "VCC_18") (pintype "power_in"))
      (node (ref "U2") (pin "31") (pinfunction "VCC_31") (pintype "power_in"))
      (node (ref "U2") (pin "42") (pinfunction "VCC_42") (pintype "power_in"))
      (node (ref "U2") (pin "7") (pinfunction "VCC_7") (pintype "power_in"))
      (node (ref "U3") (pin "13") (pinfunction "VCC_13") (pintype "power_in"))
      (node (ref "U3") (pin "41") (pinfunction "VCC_41") (pintype "power_in"))
      (node (ref "VR1") (pin "3") (pinfunction "OUT_3") (pintype "power_in"))
    )
    (net (code "84") (name "WRITE-ENABLE") (class "Default")
      (node (ref "DL2") (pin "10") (pinfunction "TAP7_10") (pintype "output"))
      (node (ref "IC2") (pin "5") (pinfunction "3A_5") (pintype "input"))
      (node (ref "U3") (pin "49") (pinfunction "~{OE}_49") (pintype "input"))
    )
    (net (code "85") (name "unconnected-(DL1-NC-Pad2)") (class "Default")
      (node (ref "DL1") (pin "2") (pinfunction "NC_2") (pintype "no_connect"))
    )
    (net (code "86") (name "unconnected-(DL1-TAP1-Pad13)") (class "Default")
      (node (ref "DL1") (pin "13") (pinfunction "TAP1_13") (pintype "output"))
    )
    (net (code "87") (name "unconnected-(DL1-TAP2-Pad3)") (class "Default")
      (node (ref "DL1") (pin "3") (pinfunction "TAP2_3") (pintype "output"))
    )
    (net (code "88") (name "unconnected-(DL1-TAP3-Pad12)") (class "Default")
      (node (ref "DL1") (pin "12") (pinfunction "TAP3_12") (pintype "output"))
    )
    (net (code "89") (name "unconnected-(DL1-TAP5-Pad11)") (class "Default")
      (node (ref "DL1") (pin "11") (pinfunction "TAP5_11") (pintype "output"))
    )
    (net (code "90") (name "unconnected-(DL1-TAP6-Pad5)") (class "Default")
      (node (ref "DL1") (pin "5") (pinfunction "TAP6_5") (pintype "output"))
    )
    (net (code "91") (name "unconnected-(DL1-TAP7-Pad10)") (class "Default")
      (node (ref "DL1") (pin "10") (pinfunction "TAP7_10") (pintype "output"))
    )
    (net (code "92") (name "unconnected-(DL1-TAP8-Pad6)") (class "Default")
      (node (ref "DL1") (pin "6") (pinfunction "TAP8_6") (pintype "output"))
    )
    (net (code "93") (name "unconnected-(DL2-NC-Pad2)") (class "Default")
      (node (ref "DL2") (pin "2") (pinfunction "NC_2") (pintype "no_connect"))
    )
    (net (code "94") (name "unconnected-(DL2-TAP1-Pad13)") (class "Default")
      (node (ref "DL2") (pin "13") (pinfunction "TAP1_13") (pintype "output"))
    )
    (net (code "95") (name "unconnected-(DL2-TAP2-Pad3)") (class "Default")
      (node (ref "DL2") (pin "3") (pinfunction "TAP2_3") (pintype "output"))
    )
    (net (code "96") (name "unconnected-(DL2-TAP3-Pad12)") (class "Default")
      (node (ref "DL2") (pin "12") (pinfunction "TAP3_12") (pintype "output"))
    )
    (net (code "97") (name "unconnected-(DL2-TAP4-Pad4)") (class "Default")
      (node (ref "DL2") (pin "4") (pinfunction "TAP4_4") (pintype "output"))
    )
    (net (code "98") (name "unconnected-(DL2-TAP5-Pad11)") (class "Default")
      (node (ref "DL2") (pin "11") (pinfunction "TAP5_11") (pintype "output"))
    )
    (net (code "99") (name "unconnected-(DL2-TAP8-Pad6)") (class "Default")
      (node (ref "DL2") (pin "6") (pinfunction "TAP8_6") (pintype "output"))
    )
    (net (code "100") (name "unconnected-(DL2-TAP9-Pad9)") (class "Default")
      (node (ref "DL2") (pin "9") (pinfunction "TAP9_9") (pintype "output"))
    )
    (net (code "101") (name "unconnected-(IC2-4Y-Pad8)") (class "Default")
      (node (ref "IC2") (pin "8") (pinfunction "4Y_8") (pintype "output"))
    )
    (net (code "102") (name "unconnected-(IC2-5Y-Pad10)") (class "Default")
      (node (ref "IC2") (pin "10") (pinfunction "5Y_10") (pintype "output"))
    )
    (net (code "103") (name "unconnected-(IC2-6Y-Pad12)") (class "Default")
      (node (ref "IC2") (pin "12") (pinfunction "6Y_12") (pintype "output"))
    )
    (net (code "104") (name "unconnected-(U1A-2Q5-Pad8)") (class "Default")
      (node (ref "U1") (pin "8") (pinfunction "2Q5_8") (pintype "output"))
    )
    (net (code "105") (name "unconnected-(U1A-2Q6-Pad9)") (class "Default")
      (node (ref "U1") (pin "9") (pinfunction "2Q6_9") (pintype "output"))
    )
    (net (code "106") (name "unconnected-(U1A-2Q7-Pad11)") (class "Default")
      (node (ref "U1") (pin "11") (pinfunction "2Q7_11") (pintype "output"))
    )
    (net (code "107") (name "unconnected-(U1A-2Q8-Pad12)") (class "Default")
      (node (ref "U1") (pin "12") (pinfunction "2Q8_12") (pintype "output"))
    )
    (net (code "108") (name "unconnected-(U2A-2Q8-Pad12)") (class "Default")
      (node (ref "U2") (pin "12") (pinfunction "2Q8_12") (pintype "output"))
    )
    (net (code "109") (name "unconnected-(U3-INT-Pad1)") (class "Default")
      (node (ref "U3") (pin "1") (pinfunction "INT_1") (pintype "output"))
    )
    (net (code "110") (name "unconnected-(U3-NC-Pad2)") (class "Default")
      (node (ref "U3") (pin "2") (pinfunction "NC_2") (pintype "no_connect"))
    )
    (net (code "111") (name "unconnected-(U3-NC-Pad25)") (class "Default")
      (node (ref "U3") (pin "25") (pinfunction "NC_25") (pintype "no_connect"))
    )
    (net (code "112") (name "unconnected-(U3-NC-Pad30)") (class "Default")
      (node (ref "U3") (pin "30") (pinfunction "NC_30") (pintype "no_connect"))
    )
    (net (code "113") (name "unconnected-(U3-NC-Pad53)") (class "Default")
      (node (ref "U3") (pin "53") (pinfunction "NC_53") (pintype "no_connect"))
    )
    (net (code "114") (name "unconnected-(U3-VRTCBAT-Pad28)") (class "Default")
      (node (ref "U3") (pin "28") (pinfunction "VRTCBAT_28") (pintype "passive"))
    )
    (net (code "115") (name "unconnected-(U3-VRTCCAP-Pad29)") (class "Default")
      (node (ref "U3") (pin "29") (pinfunction "VRTCCAP_29") (pintype "passive"))
    )
    (net (code "116") (name "unconnected-(U3-XIN-Pad27)") (class "Default")
      (node (ref "U3") (pin "27") (pinfunction "XIN_27") (pintype "passive"))
    )
    (net (code "117") (name "unconnected-(U3-XOUT-Pad26)") (class "Default")
      (node (ref "U3") (pin "26") (pinfunction "XOUT_26") (pintype "passive"))
    )
    (net (code "118") (name "unconnected-(U3-~{HSB}-Pad54)") (class "Default")
      (node (ref "U3") (pin "54") (pinfunction "~{HSB}_54") (pintype "bidirectional"))
    )
    (net (code "119") (name "unconnected-(U4A-2Q5-Pad19)") (class "Default")
      (node (ref "U4") (pin "19") (pinfunction "2Q5_19") (pintype "output"))
    )
    (net (code "120") (name "unconnected-(U4A-2Q6-Pad20)") (class "Default")
      (node (ref "U4") (pin "20") (pinfunction "2Q6_20") (pintype "output"))
    )
    (net (code "121") (name "unconnected-(U4A-2Q7-Pad22)") (class "Default")
      (node (ref "U4") (pin "22") (pinfunction "2Q7_22") (pintype "output"))
    )
    (net (code "122") (name "unconnected-(U4A-2Q8-Pad23)") (class "Default")
      (node (ref "U4") (pin "23") (pinfunction "2Q8_23") (pintype "output"))
    )
    (net (code "123") (name "unconnected-(X1-Pad1)") (class "Default")
      (node (ref "X1") (pin "1") (pinfunction "1_1") (pintype "passive"))
    )
    (net (code "124") (name "unconnected-(X1-Pad2)") (class "Default")
      (node (ref "X1") (pin "2") (pinfunction "2_2") (pintype "passive"))
    )
    (net (code "125") (name "unconnected-(X2-Pad1)") (class "Default")
      (node (ref "X2") (pin "1") (pinfunction "1_1") (pintype "passive"))
    )
    (net (code "126") (name "unconnected-(X2-Pad2)") (class "Default")
      (node (ref "X2") (pin "2") (pinfunction "2_2") (pintype "passive"))
    )
    (net (code "127") (name "unconnected-(X3-Pad1)") (class "Default")
      (node (ref "X3") (pin "1") (pinfunction "1_1") (pintype "passive"))
    )
    (net (code "128") (name "unconnected-(X3-Pad2)") (class "Default")
      (node (ref "X3") (pin "2") (pinfunction "2_2") (pintype "passive"))
    )
    (net (code "129") (name "unconnected-(X4-Pad1)") (class "Default")
      (node (ref "X4") (pin "1") (pinfunction "1_1") (pintype "passive"))
    )
    (net (code "130") (name "unconnected-(X4-Pad2)") (class "Default")
      (node (ref "X4") (pin "2") (pinfunction "2_2") (pintype "passive"))
    )
    (net (code "131") (name "unconnected-(X4-Pad4)") (class "Default")
      (node (ref "X4") (pin "4") (pinfunction "4_4") (pintype "passive"))
    )
    (net (code "132") (name "unconnected-(X5-Pad1)") (class "Default")
      (node (ref "X5") (pin "1") (pinfunction "1_1") (pintype "passive"))
    )
    (net (code "133") (name "unconnected-(X5-Pad2)") (class "Default")
      (node (ref "X5") (pin "2") (pinfunction "2_2") (pintype "passive"))
    )
    (net (code "134") (name "unconnected-(X5-Pad16)") (class "Default")
      (node (ref "X5") (pin "16") (pinfunction "16_16") (pintype "passive"))
    )
    (net (code "135") (name "~{MEM-DONE}") (class "Default")
      (node (ref "DL2") (pin "8") (pinfunction "TAP10_8") (pintype "output"))
      (node (ref "IC2") (pin "3") (pinfunction "2A_3") (pintype "input"))
    )
    (net (code "136") (name "~{STROBE}") (class "Default")
      (node (ref "DL1") (pin "8") (pinfunction "TAP10_8") (pintype "output"))
      (node (ref "IC2") (pin "1") (pinfunction "1A_1") (pintype "input"))
    )
    (net (code "137") (name "~{WRITE-ENABLE}") (class "Default")
      (node (ref "IC2") (pin "6") (pinfunction "3Y_6") (pintype "output"))
      (node (ref "U3") (pin "19") (pinfunction "~{WE}_19") (pintype "input"))
    )
  )
)
